# SparkFun_Qwiic_Distance_-_VL53L4CX.net
KiCad netlist of a schematic drawn in EAGLE
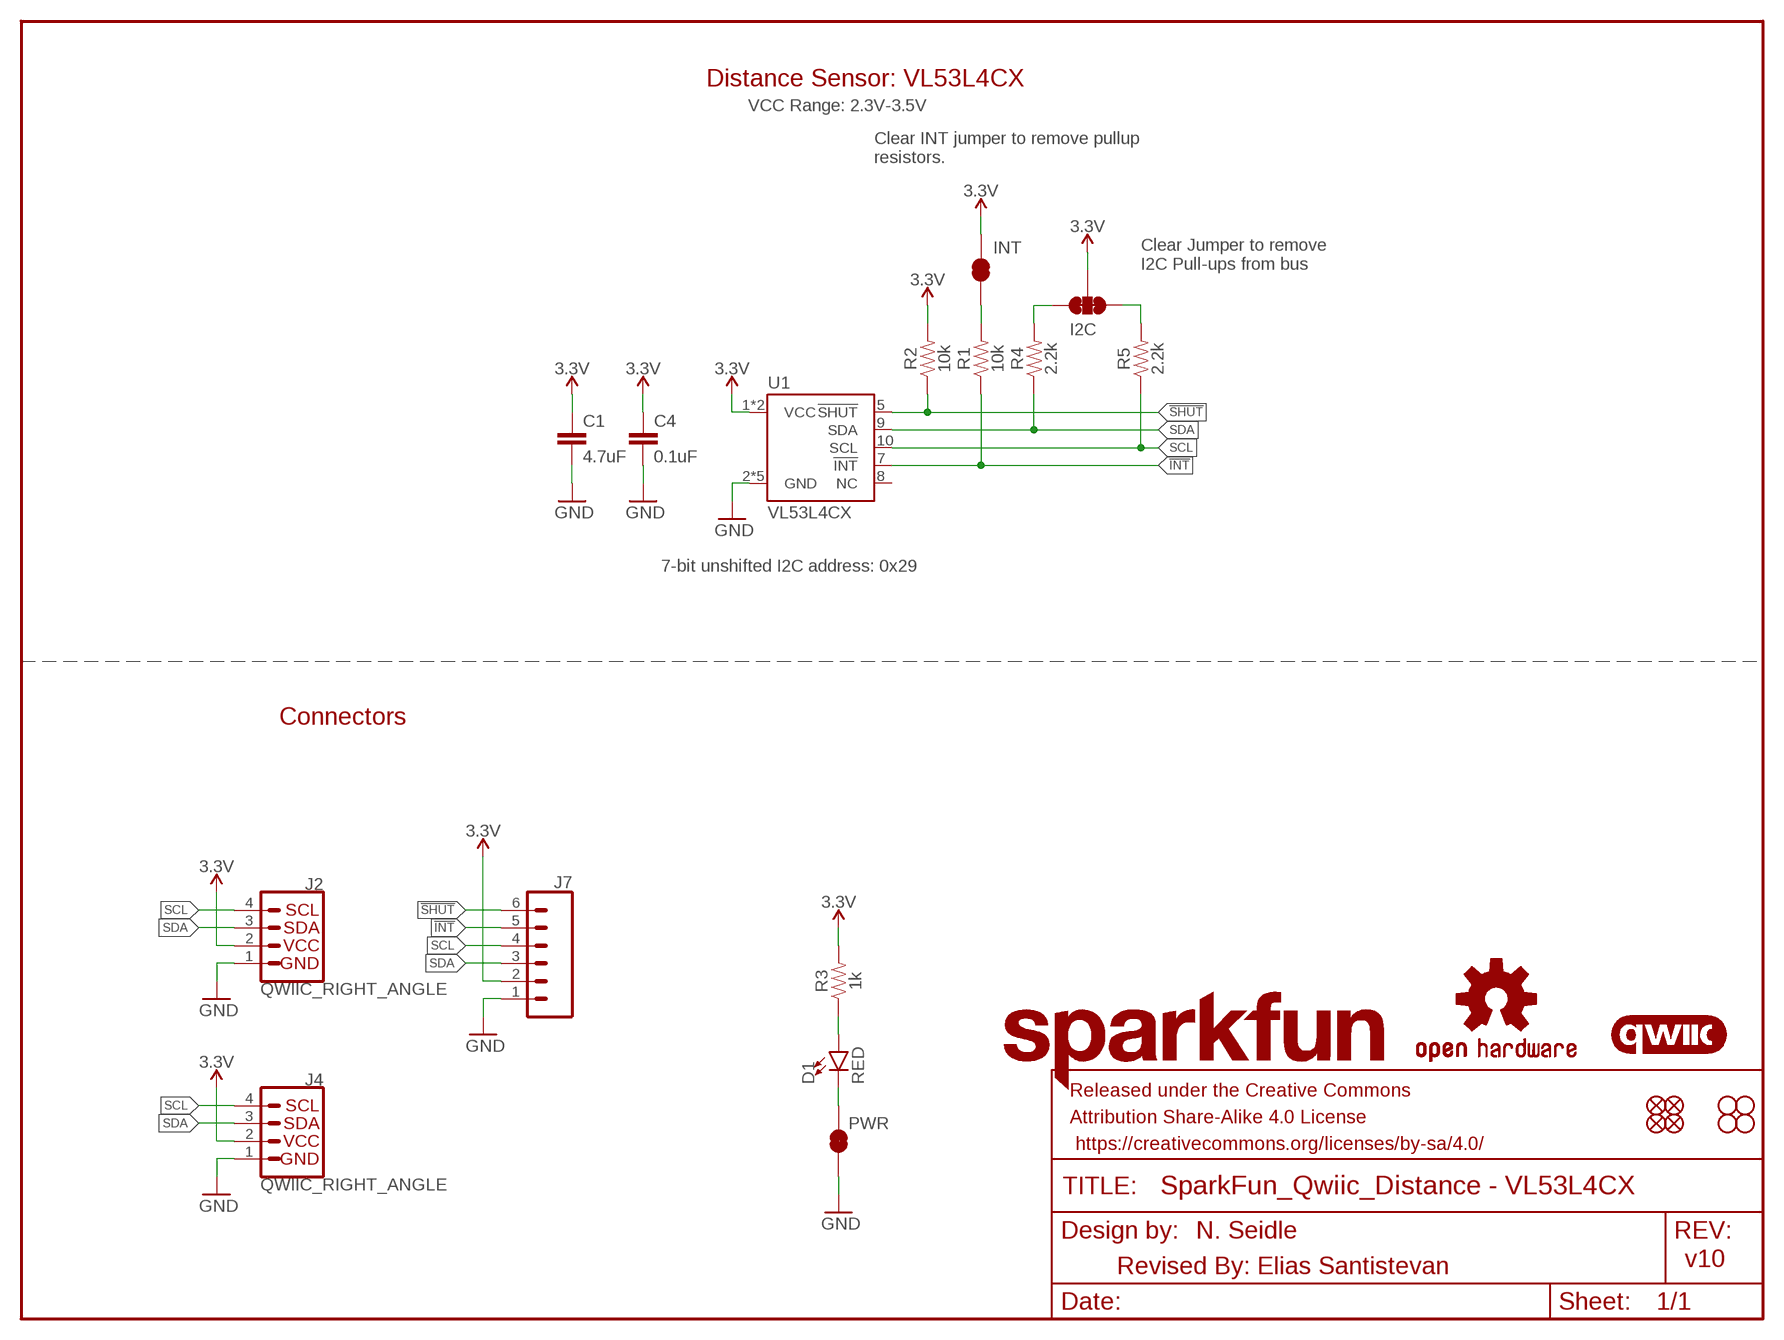
[diagram p0: schematic, sheet 1]

(export (version "E")
  (design (tool "Eeschema 10.0.6"))
  (components
    (comp (ref "C1")
      (value "4.7uF")
      (footprint "eagle-import:0603")
      (libsource (lib "eagle-import") (part "4.7UF-0603-6.3V-(10%)"))
    )
    (comp (ref "C4")
      (value "0.1uF")
      (footprint "eagle-import:0603")
      (libsource (lib "eagle-import") (part "0.1UF-0603-25V-(+80/-20%)"))
    )
    (comp (ref "D1")
      (value "RED")
      (footprint "eagle-import:LED-0603")
      (libsource (lib "eagle-import") (part "LED-RED0603"))
    )
    (comp (ref "FRAME1")
      (value "FRAME-LETTER")
      (footprint "eagle-import:CREATIVE_COMMONS")
      (libsource (lib "eagle-import") (part "FRAME-LETTER"))
    )
    (comp (ref "I2C")
      (value "JUMPER-SMT_3_2-NC_TRACE_SILK")
      (footprint "eagle-import:SMT-JUMPER_3_2-NC_TRACE_SILK")
      (libsource (lib "eagle-import") (part "JUMPER-SMT_3_2-NC_TRACE_SILK"))
    )
    (comp (ref "J2")
      (value "QWIIC_RIGHT_ANGLE")
      (footprint "eagle-import:JST04_1MM_RA")
      (libsource (lib "eagle-import") (part "QWIIC_CONNECTORJS-1MM"))
    )
    (comp (ref "J4")
      (value "QWIIC_RIGHT_ANGLE")
      (footprint "eagle-import:JST04_1MM_RA")
      (libsource (lib "eagle-import") (part "QWIIC_CONNECTORJS-1MM"))
    )
    (comp (ref "J7")
      (value "CONN_06NO_SILK_NO_POP")
      (footprint "eagle-import:1X06_NO_SILK")
      (libsource (lib "eagle-import") (part "CONN_06NO_SILK_NO_POP"))
    )
    (comp (ref "JP1")
      (value "FIDUCIALUFIDUCIAL")
      (footprint "eagle-import:MICRO-FIDUCIAL")
      (libsource (lib "eagle-import") (part "FIDUCIALUFIDUCIAL"))
    )
    (comp (ref "JP2")
      (value "FIDUCIALUFIDUCIAL")
      (footprint "eagle-import:MICRO-FIDUCIAL")
      (libsource (lib "eagle-import") (part "FIDUCIALUFIDUCIAL"))
    )
    (comp (ref "JP3")
      (value "STAND-OFF")
      (footprint "eagle-import:STAND-OFF")
      (libsource (lib "eagle-import") (part "STAND-OFF"))
    )
    (comp (ref "JP4")
      (value "STAND-OFF")
      (footprint "eagle-import:STAND-OFF")
      (libsource (lib "eagle-import") (part "STAND-OFF"))
    )
    (comp (ref "JP5")
      (value "FIDUCIALUFIDUCIAL")
      (footprint "eagle-import:MICRO-FIDUCIAL")
      (libsource (lib "eagle-import") (part "FIDUCIALUFIDUCIAL"))
    )
    (comp (ref "JP6")
      (value "FIDUCIALUFIDUCIAL")
      (footprint "eagle-import:MICRO-FIDUCIAL")
      (libsource (lib "eagle-import") (part "FIDUCIALUFIDUCIAL"))
    )
    (comp (ref "JP7")
      (value "STAND-OFF")
      (footprint "eagle-import:STAND-OFF")
      (libsource (lib "eagle-import") (part "STAND-OFF"))
    )
    (comp (ref "JP8")
      (value "STAND-OFF")
      (footprint "eagle-import:STAND-OFF")
      (libsource (lib "eagle-import") (part "STAND-OFF"))
    )
    (comp (ref "JP9")
      (value "INT")
      (footprint "eagle-import:SMT-JUMPER_2_NC_TRACE_SILK")
      (libsource (lib "eagle-import") (part "JUMPER-SMT_2_NC_TRACE_SILK"))
    )
    (comp (ref "LOGO1")
      (value "OSHW-LOGOMINI")
      (footprint "eagle-import:OSHW-LOGO-MINI")
      (libsource (lib "eagle-import") (part "OSHW-LOGOMINI"))
    )
    (comp (ref "LOGO2")
      (value "SFE_LOGO_NAME.1_INCH")
      (footprint "eagle-import:SFE_LOGO_NAME_.1")
      (libsource (lib "eagle-import") (part "SFE_LOGO_NAME.1_INCH"))
    )
    (comp (ref "LOGO3")
      (value "QWIIC_LOGO_4MM")
      (footprint "eagle-import:QWIIC_4MM")
      (libsource (lib "eagle-import") (part "QWIIC_LOGO_4MM"))
    )
    (comp (ref "PWR")
      (value "INT")
      (footprint "eagle-import:SMT-JUMPER_2_NC_TRACE_SILK")
      (libsource (lib "eagle-import") (part "JUMPER-SMT_2_NC_TRACE_SILK"))
    )
    (comp (ref "R1")
      (value "10k")
      (footprint "eagle-import:0603")
      (libsource (lib "eagle-import") (part "10KOHM-0603-1/10W-1%"))
    )
    (comp (ref "R2")
      (value "10k")
      (footprint "eagle-import:0603")
      (libsource (lib "eagle-import") (part "10KOHM-0603-1/10W-1%"))
    )
    (comp (ref "R3")
      (value "1k")
      (footprint "eagle-import:0603")
      (libsource (lib "eagle-import") (part "1KOHM-0603-1/10W-1%"))
    )
    (comp (ref "R4")
      (value "2.2k")
      (footprint "eagle-import:0603")
      (libsource (lib "eagle-import") (part "2.2KOHM-0603-1/10W-1%"))
    )
    (comp (ref "R5")
      (value "2.2k")
      (footprint "eagle-import:0603")
      (libsource (lib "eagle-import") (part "2.2KOHM-0603-1/10W-1%"))
    )
    (comp (ref "U1")
      (value "VL53L4CX")
      (footprint "eagle-import:VL53L4CX")
      (libsource (lib "eagle-import") (part "VL53L4CX"))
    )
  )
  (nets
    (net (code "1") (name "/~{INT}") (class "Default")
      (node (ref "J7") (pin "5") (pinfunction "5_5") (pintype "passive"))
      (node (ref "R1") (pin "1") (pinfunction "1_1") (pintype "passive"))
      (node (ref "U1") (pin "7") (pinfunction "~{INT}_7") (pintype "output"))
    )
    (net (code "2") (name "/~{SHUT}") (class "Default")
      (node (ref "J7") (pin "6") (pinfunction "6_6") (pintype "passive"))
      (node (ref "R2") (pin "1") (pinfunction "1_1") (pintype "passive"))
      (node (ref "U1") (pin "5") (pinfunction "~{SHUT}_5") (pintype "input"))
    )
    (net (code "3") (name "3.3V") (class "Default")
      (node (ref "C1") (pin "1") (pinfunction "1_1") (pintype "passive"))
      (node (ref "C4") (pin "1") (pinfunction "1_1") (pintype "passive"))
      (node (ref "I2C") (pin "2") (pinfunction "2_2") (pintype "passive"))
      (node (ref "J2") (pin "2") (pinfunction "2_2") (pintype "power_in"))
      (node (ref "J4") (pin "2") (pinfunction "2_2") (pintype "power_in"))
      (node (ref "J7") (pin "2") (pinfunction "2_2") (pintype "passive"))
      (node (ref "JP9") (pin "2") (pinfunction "2_2") (pintype "passive"))
      (node (ref "R2") (pin "2") (pinfunction "2_2") (pintype "passive"))
      (node (ref "R3") (pin "2") (pinfunction "2_2") (pintype "passive"))
      (node (ref "U1") (pin "1") (pinfunction "VCC_1") (pintype "power_in"))
      (node (ref "U1") (pin "11") (pinfunction "VCC_11") (pintype "power_in"))
    )
    (net (code "4") (name "GND") (class "Default")
      (node (ref "C1") (pin "2") (pinfunction "2_2") (pintype "passive"))
      (node (ref "C4") (pin "2") (pinfunction "2_2") (pintype "passive"))
      (node (ref "J2") (pin "1") (pinfunction "1_1") (pintype "power_in"))
      (node (ref "J4") (pin "1") (pinfunction "1_1") (pintype "power_in"))
      (node (ref "J7") (pin "1") (pinfunction "1_1") (pintype "passive"))
      (node (ref "PWR") (pin "1") (pinfunction "1_1") (pintype "passive"))
      (node (ref "U1") (pin "12") (pinfunction "GND_12") (pintype "power_in"))
      (node (ref "U1") (pin "2") (pinfunction "GND_2") (pintype "power_in"))
      (node (ref "U1") (pin "3") (pinfunction "GND_3") (pintype "power_in"))
      (node (ref "U1") (pin "4") (pinfunction "GND_4") (pintype "power_in"))
      (node (ref "U1") (pin "6") (pinfunction "GND_6") (pintype "power_in"))
    )
    (net (code "5") (name "Net-(D1-PadA)") (class "Default")
      (node (ref "D1") (pin "A") (pinfunction "A_A") (pintype "passive"))
      (node (ref "R3") (pin "1") (pinfunction "1_1") (pintype "passive"))
    )
    (net (code "6") (name "Net-(D1-PadC)") (class "Default")
      (node (ref "D1") (pin "C") (pinfunction "C_C") (pintype "passive"))
      (node (ref "PWR") (pin "2") (pinfunction "2_2") (pintype "passive"))
    )
    (net (code "7") (name "Net-(I2C-Pad1)") (class "Default")
      (node (ref "I2C") (pin "1") (pinfunction "1_1") (pintype "passive"))
      (node (ref "R5") (pin "2") (pinfunction "2_2") (pintype "passive"))
    )
    (net (code "8") (name "Net-(I2C-Pad3)") (class "Default")
      (node (ref "I2C") (pin "3") (pinfunction "3_3") (pintype "passive"))
      (node (ref "R4") (pin "2") (pinfunction "2_2") (pintype "passive"))
    )
    (net (code "9") (name "Net-(JP9-Pad1)") (class "Default")
      (node (ref "JP9") (pin "1") (pinfunction "1_1") (pintype "passive"))
      (node (ref "R1") (pin "2") (pinfunction "2_2") (pintype "passive"))
    )
    (net (code "10") (name "SCL") (class "Default")
      (node (ref "J2") (pin "4") (pinfunction "4_4") (pintype "passive"))
      (node (ref "J4") (pin "4") (pinfunction "4_4") (pintype "passive"))
      (node (ref "J7") (pin "4") (pinfunction "4_4") (pintype "passive"))
      (node (ref "R5") (pin "1") (pinfunction "1_1") (pintype "passive"))
      (node (ref "U1") (pin "10") (pinfunction "SCL_10") (pintype "bidirectional"))
    )
    (net (code "11") (name "SDA") (class "Default")
      (node (ref "J2") (pin "3") (pinfunction "3_3") (pintype "passive"))
      (node (ref "J4") (pin "3") (pinfunction "3_3") (pintype "passive"))
      (node (ref "J7") (pin "3") (pinfunction "3_3") (pintype "passive"))
      (node (ref "R4") (pin "1") (pinfunction "1_1") (pintype "passive"))
      (node (ref "U1") (pin "9") (pinfunction "SDA_9") (pintype "bidirectional"))
    )
    (net (code "12") (name "unconnected-(U1-NC-Pad8)") (class "Default")
      (node (ref "U1") (pin "8") (pinfunction "NC_8") (pintype "no_connect"))
    )
  )
)
